# Button.net
KiCad netlist of a schematic drawn in Altium Designer
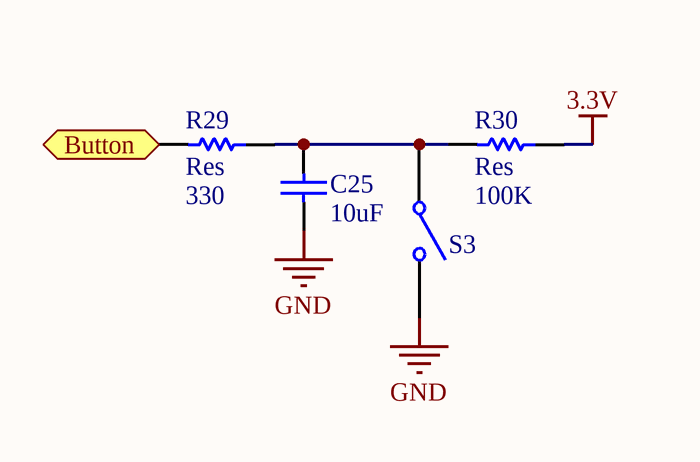
[diagram p0: Button.SchDoc]

(export (version "E")
  (design (tool "Eeschema 10.0.6"))
  (components
    (comp (ref "C25")
      (value "10uF")
      (footprint "2012[0805]")
      (description "Capacitor")
      (fields (field (name "Comment") "Cap_UP") (field (name "PUBLISHER") "Altium Limited"))
      (libsource (lib "KN2CLib") (part "Cap_UP"))
    )
    (comp (ref "R29")
      (value "Res")
      (footprint "2012[0805]")
      (description "Semiconductor Resistor")
      (fields (field (name "ALTIUM_VALUE") "330") (field (name "PUBLISHER") "Altium Limited"))
      (libsource (lib "KN2CLib") (part "Res"))
    )
    (comp (ref "R30")
      (value "Res")
      (footprint "2012[0805]")
      (description "Semiconductor Resistor")
      (fields (field (name "ALTIUM_VALUE") "100K") (field (name "PUBLISHER") "Altium Limited"))
      (libsource (lib "KN2CLib") (part "Res"))
    )
    (comp (ref "S3")
      (value "SW-SPST")
      (footprint "PUSH-BUT")
      (description "Single-Pole, Single-Throw Switch")
      (fields (field (name "PUBLISHER") "Altium Limited"))
      (libsource (lib "KN2CLib") (part "SW-SPST"))
    )
  )
  (nets
    (net (code "1") (name "/Button") (class "Default")
      (node (ref "R29") (pin "2") (pinfunction "2_2") (pintype "passive"))
    )
    (net (code "2") (name "3.3V") (class "Default")
      (node (ref "R30") (pin "1") (pinfunction "1_1") (pintype "passive"))
    )
    (net (code "3") (name "GND") (class "Default")
      (node (ref "C25") (pin "1") (pinfunction "1_1") (pintype "passive"))
      (node (ref "S3") (pin "2") (pinfunction "NO_2") (pintype "passive"))
    )
    (net (code "4") (name "Net-(S3-COMMON)") (class "Default")
      (node (ref "C25") (pin "2") (pinfunction "2_2") (pintype "passive"))
      (node (ref "R29") (pin "1") (pinfunction "1_1") (pintype "passive"))
      (node (ref "R30") (pin "2") (pinfunction "2_2") (pintype "passive"))
      (node (ref "S3") (pin "1") (pinfunction "COMMON_1") (pintype "passive"))
    )
  )
)
